# power_12V.net
KiCad netlist of a schematic drawn in Altium Designer
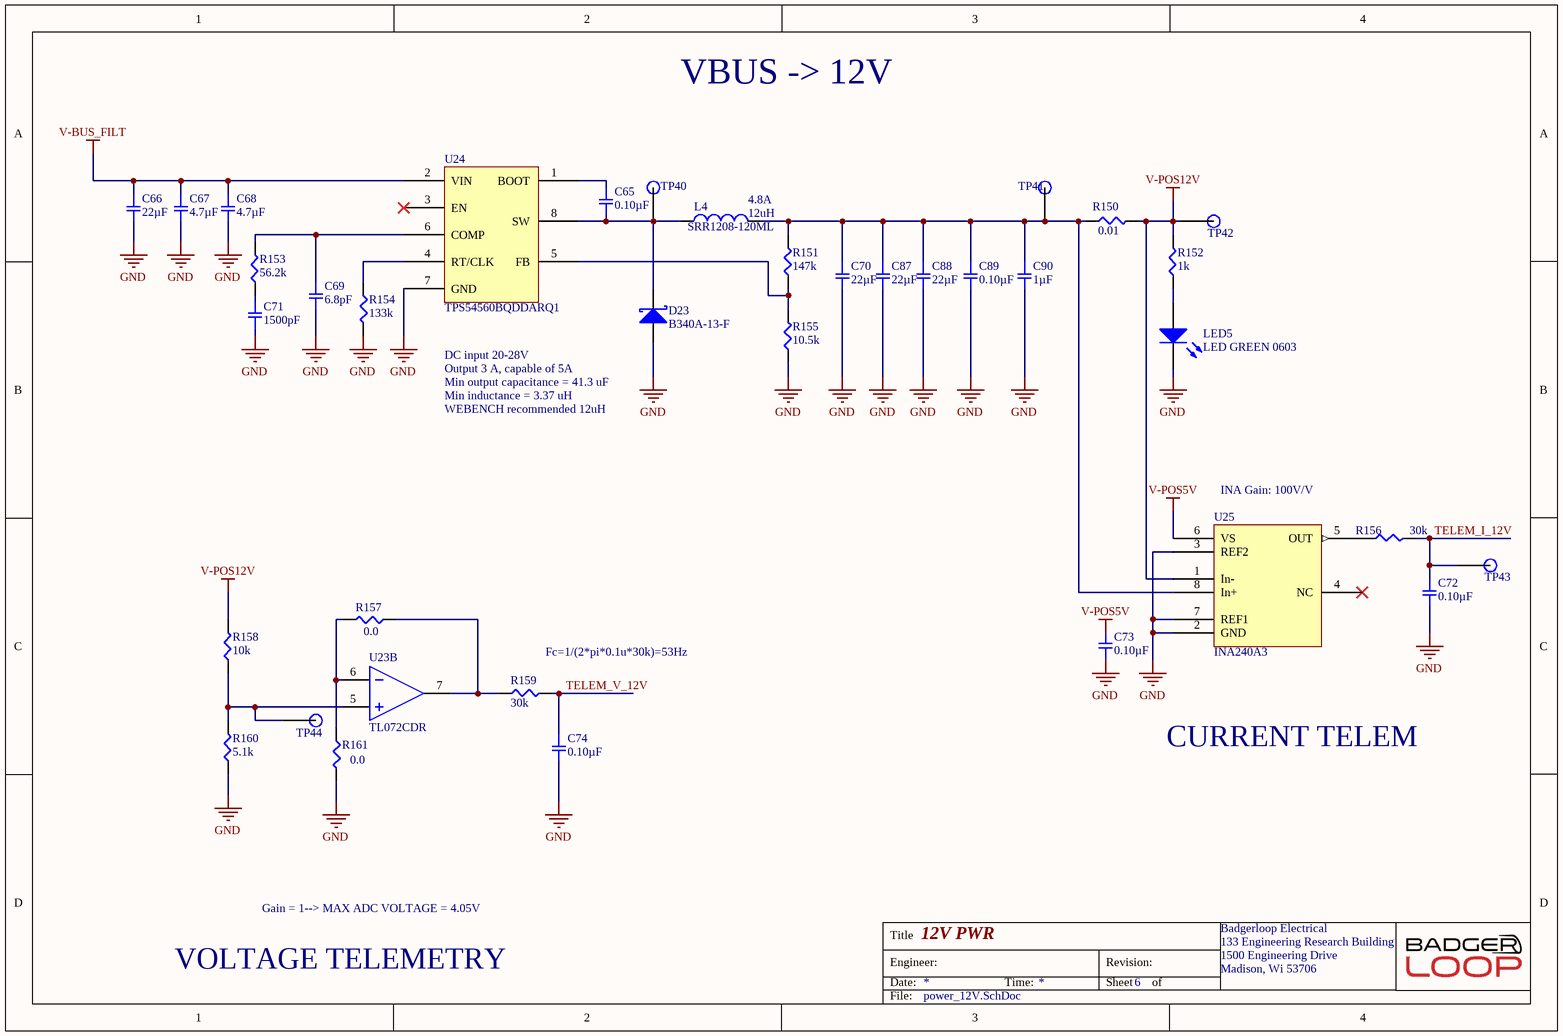
[diagram p0: power_12V.SchDoc]

(export (version "E")
  (design (tool "Eeschema 10.0.6"))
  (components
    (comp (ref "C65")
      (value "0.10µF")
      (footprint "SMD-0805C")
      (description "CAP CER 0.1UF 50V X7R 0805")
      (fields
        (field (name "DIGI-KEY PART NUMBER") "490-11955-1-ND")
        (field (name "PART NUMBER") "GCD21BR71H104KA01L")
      )
      (libsource (lib "capacitors") (part "GCD21BR71H104KA01L"))
    )
    (comp (ref "C66")
      (value "22µF")
      (footprint "SMD-1206C")
      (description "CAP CER 22UF 25V X5R 1206")
      (fields
        (field (name "DIGI-KEY PART NUMBER") "490-12451-1-ND")
        (field (name "PART NUMBER") "GRT31CR61E226ME01L")
      )
      (libsource (lib "capacitors") (part "GRT31CR61E226ME01L"))
    )
    (comp (ref "C67")
      (value "4.7µF")
      (footprint "SMD-0805C")
      (description "CAP CER 4.7UF 50V X5R 0805")
      (fields
        (field (name "DIGI-KEY PART NUMBER") "490-12395-1-ND")
        (field (name "PART NUMBER") "GRT21BR61H475ME13L")
      )
      (libsource (lib "capacitors") (part "GRT21BR61H475ME13L"))
    )
    (comp (ref "C68")
      (value "4.7µF")
      (footprint "SMD-0805C")
      (description "CAP CER 4.7UF 50V X5R 0805")
      (fields
        (field (name "DIGI-KEY PART NUMBER") "490-12395-1-ND")
        (field (name "PART NUMBER") "GRT21BR61H475ME13L")
      )
      (libsource (lib "capacitors") (part "GRT21BR61H475ME13L"))
    )
    (comp (ref "C69")
      (value "6.8pF")
      (footprint "SMD-0805C")
      (description "CAP CER 6.8PF 100V NP0 0805")
      (fields
        (field (name "DIGI-KEY PART NUMBER") "490-3596-1-ND")
        (field (name "PART NUMBER") "GQM2195C2A6R8CB01D")
      )
      (libsource (lib "capacitors") (part "GQM2195C2A6R8CB01D"))
    )
    (comp (ref "C70")
      (value "22µF")
      (footprint "SMD-1206C")
      (description "CAP CER 22UF 25V X5R 1206")
      (fields
        (field (name "DIGI-KEY PART NUMBER") "490-12451-1-ND")
        (field (name "PART NUMBER") "GRT31CR61E226ME01L")
      )
      (libsource (lib "capacitors") (part "GRT31CR61E226ME01L"))
    )
    (comp (ref "C71")
      (value "1500pF")
      (footprint "SMD-0805C")
      (description "CAP CER 1500PF 50V NP0 0805")
      (fields
        (field (name "DIGI-KEY PART NUMBER") "490-7772-1-ND")
        (field (name "PART NUMBER") "GRM2165C1H152FA01D")
      )
      (libsource (lib "capacitors") (part "GRM2165C1H152FA01D"))
    )
    (comp (ref "C72")
      (value "0.10µF")
      (footprint "SMD-0805C")
      (description "CAP CER 0.1UF 16V X7R 0805")
      (fields
        (field (name "DIGI-KEY PART NUMBER") "490-1683-1-ND")
        (field (name "PART NUMBER") "GRM219R71C104KA01D")
      )
      (libsource (lib "capacitors") (part "GRM219R71C104KA01D"))
    )
    (comp (ref "C73")
      (value "0.10µF")
      (footprint "SMD-0805C")
      (description "CAP CER 0.1UF 10V U2J 0805")
      (fields
        (field (name "DIGI-KEY PART NUMBER") "490-11592-1-ND")
        (field (name "PART NUMBER") "GRM21B7U1A104JA01L")
      )
      (libsource (lib "capacitors") (part "GRM21B7U1A104JA01L"))
    )
    (comp (ref "C74")
      (value "0.10µF")
      (footprint "SMD-0805C")
      (description "CAP CER 0.1UF 16V X7R 0805")
      (fields
        (field (name "DIGI-KEY PART NUMBER") "490-1683-1-ND")
        (field (name "PART NUMBER") "GRM219R71C104KA01D")
      )
      (libsource (lib "capacitors") (part "GRM219R71C104KA01D"))
    )
    (comp (ref "C87")
      (value "22µF")
      (footprint "SMD-1206C")
      (description "CAP CER 22UF 25V X5R 1206")
      (fields
        (field (name "DIGI-KEY PART NUMBER") "490-12451-1-ND")
        (field (name "PART NUMBER") "GRT31CR61E226ME01L")
      )
      (libsource (lib "capacitors") (part "GRT31CR61E226ME01L"))
    )
    (comp (ref "C88")
      (value "22µF")
      (footprint "SMD-1206C")
      (description "CAP CER 22UF 25V X5R 1206")
      (fields
        (field (name "DIGI-KEY PART NUMBER") "490-12451-1-ND")
        (field (name "PART NUMBER") "GRT31CR61E226ME01L")
      )
      (libsource (lib "capacitors") (part "GRT31CR61E226ME01L"))
    )
    (comp (ref "C89")
      (value "0.10µF")
      (footprint "SMD-0805C")
      (description "CAP CER 0.1UF 10V U2J 0805")
      (fields
        (field (name "DIGI-KEY PART NUMBER") "490-11592-1-ND")
        (field (name "PART NUMBER") "GRM21B7U1A104JA01L")
      )
      (libsource (lib "capacitors") (part "GRM21B7U1A104JA01L"))
    )
    (comp (ref "C90")
      (value "1µF")
      (footprint "SMD-0805C")
      (description "CAP CER 1UF 50V X7R 0805")
      (fields
        (field (name "DIGI-KEY PART NUMBER") "490-4736-1-ND")
        (field (name "PART NUMBER") "GRM21BR71H105KA12L")
      )
      (libsource (lib "capacitors") (part "GRM21BR71H105KA12L"))
    )
    (comp (ref "D23")
      (value "B340A-13-F")
      (footprint "DIOM4326X20N")
      (description "DIODE SCHOTTKY 40V 3A SMA")
      (fields (field (name "MANUFACTURER") "Diodes") (field (name "VOLTAGE") "40V"))
      (libsource (lib "misc") (part "B340A-13-F"))
    )
    (comp (ref "L4")
      (value "SRR1208-120ML")
      (footprint "INDP127127X83N")
      (description "BOURNS - SRR1208-120ML - INDUCTOR, SHIELDED, 12UH, 6.5A, 20%, SMD")
      (fields
        (field (name "MANUFACTURER") "Bourns")
        (field (name "TOLERANCE") "20%")
        (field (name "CURRENT RATING") "4.8A")
        (field (name "INDUCTANCE") "12uH")
      )
      (libsource (lib "inductor") (part "SRR1208-120ML"))
    )
    (comp (ref "LED5")
      (value "LED GREEN 0603")
      (footprint "LED 0603 GREEN")
      (fields (field (name "MANUFACTURER") "Lite-On Inc."))
      (libsource (lib "misc") (part "LED GREEN 0603"))
    )
    (comp (ref "R150")
      (value "0.01")
      (footprint "SMD-1206-RES")
      (description "RES SMD 0.01 OHM 1% 1/2W 1206")
      (fields
        (field (name "PART NUMBER") "ERJ-MP2KF10MU")
        (field (name "DIGI-KEY PART NUMBER") "P19322CT-ND")
      )
      (libsource (lib "resistors") (part "ERJ-MP2KF10MU"))
    )
    (comp (ref "R151")
      (value "147k")
      (footprint "SMD-0805-RES")
      (description "RES SMD 147K OHM 1% 1/8W 0805")
      (fields
        (field (name "PART NUMBER") "ERJ-6ENF1473V")
        (field (name "DIGI-KEY PART NUMBER") "P147KCCT-ND")
      )
      (libsource (lib "resistors") (part "ERJ-6ENF1473V"))
    )
    (comp (ref "R152")
      (value "1k")
      (footprint "SMD-0805-RES")
      (description "RES SMD 1K OHM 5% 1/2W 0805")
      (fields
        (field (name "PART NUMBER") "ERJ-P06J102V")
        (field (name "DIGI-KEY PART NUMBER") "P1.0KADCT-ND")
      )
      (libsource (lib "resistors") (part "ERJ-P06J102V"))
    )
    (comp (ref "R153")
      (value "56.2k")
      (footprint "SMD-0805-RES")
      (description "RES SMD 56.2K OHM 1% 1/8W 0805")
      (fields
        (field (name "PART NUMBER") "ERJ-6ENF5622V")
        (field (name "DIGI-KEY PART NUMBER") "P56.2KCCT-ND")
      )
      (libsource (lib "resistors") (part "ERJ-6ENF5622V"))
    )
    (comp (ref "R154")
      (value "133k")
      (footprint "SMD-0805-RES")
      (description "RES SMD 133K OHM 1% 1/8W 0805")
      (fields
        (field (name "PART NUMBER") "ERJ-6ENF1333V")
        (field (name "DIGI-KEY PART NUMBER") "P133KCCT-ND")
      )
      (libsource (lib "resistors") (part "ERJ-6ENF1333V"))
    )
    (comp (ref "R155")
      (value "10.5k")
      (footprint "SMD-0805-RES")
      (description "RES SMD 10.5K OHM 1% 1/8W 0805")
      (fields
        (field (name "PART NUMBER") "ERJ-6ENF1052V")
        (field (name "DIGI-KEY PART NUMBER") "P10.5KCCT-ND")
      )
      (libsource (lib "resistors") (part "ERJ-6ENF1052V"))
    )
    (comp (ref "R156")
      (value "30k")
      (footprint "SMD-0805-RES")
      (description "RES SMD 30K OHM 1% 1/8W 0805")
      (fields
        (field (name "PART NUMBER") "ERJ-6ENF3002V")
        (field (name "DIGI-KEY PART NUMBER") "P30.0KCCT-ND")
      )
      (libsource (lib "resistors") (part "ERJ-6ENF3002V"))
    )
    (comp (ref "R157")
      (value "0.0")
      (footprint "SMD-0805-RES")
      (description "RES SMD 0.0 OHM JUMPER 1/8W 0805")
      (fields (field (name "PART NUMBER") "ERJ-6GEY0R00V") (field (name "DIGI-KEY PART NUMBER") "P0.0ACT-ND"))
      (libsource (lib "resistors") (part "ERJ-6GEY0R00V"))
    )
    (comp (ref "R158")
      (value "10k")
      (footprint "SMD-0805-RES")
      (description "RES SMD 10K OHM 5% 1/2W 0805")
      (fields (field (name "PART NUMBER") "ERJ-P06J103V") (field (name "DIGI-KEY PART NUMBER") "P10KADCT-ND"))
      (libsource (lib "resistors") (part "ERJ-P06J103V"))
    )
    (comp (ref "R159")
      (value "30k")
      (footprint "SMD-0805-RES")
      (description "RES SMD 30K OHM 5% 1/2W 0805")
      (fields (field (name "PART NUMBER") "ERJ-P06J303V") (field (name "DIGI-KEY PART NUMBER") "P30KADCT-ND"))
      (libsource (lib "resistors") (part "ERJ-P06J303V"))
    )
    (comp (ref "R160")
      (value "5.1k")
      (footprint "SMD-0805-RES")
      (description "RES SMD 5.1K OHM 1% 1/8W 0805")
      (fields
        (field (name "PART NUMBER") "ERJ-6ENF5101V")
        (field (name "DIGI-KEY PART NUMBER") "P5.10KCCT-ND")
      )
      (libsource (lib "resistors") (part "ERJ-6ENF5101V"))
    )
    (comp (ref "R161")
      (value "0.0")
      (footprint "SMD-0805-RES")
      (description "RES SMD 0.0 OHM JUMPER 1/8W 0805")
      (fields (field (name "PART NUMBER") "ERJ-6GEY0R00V") (field (name "DIGI-KEY PART NUMBER") "P0.0ACT-ND"))
      (libsource (lib "resistors") (part "ERJ-6GEY0R00V"))
    )
    (comp (ref "TP40")
      (value "TP")
      (footprint "Test Point")
      (description "SMD TEST POINT")
      (libsource (lib "misc") (part "TP"))
    )
    (comp (ref "TP41")
      (value "TP")
      (footprint "Test Point")
      (description "SMD TEST POINT")
      (libsource (lib "misc") (part "TP"))
    )
    (comp (ref "TP42")
      (value "TP")
      (footprint "Test Point")
      (description "SMD TEST POINT")
      (libsource (lib "misc") (part "TP"))
    )
    (comp (ref "TP43")
      (value "TP")
      (footprint "Test Point")
      (description "SMD TEST POINT")
      (libsource (lib "misc") (part "TP"))
    )
    (comp (ref "TP44")
      (value "TP")
      (footprint "Test Point")
      (description "SMD TEST POINT")
      (libsource (lib "misc") (part "TP"))
    )
    (comp (ref "U23")
      (value "TL072CDR")
      (footprint "SOP127P600X175-8N")
      (description "IC OPAMP JFET 3MHZ 8SOIC")
      (fields (field (name "MANUFACTURER") "Texas Instruments"))
      (libsource (lib "ic") (part "TL072CDR"))
    )
    (comp (ref "U24")
      (value "TPS54560BQDDARQ1")
      (footprint "SOP127P600X175-8N - Thermal Pad")
      (description "IC REG BUCK SPLT ADJ 5A 8PWRSOIC")
      (fields (field (name "MANUFACTURER") "Texas Instruments"))
      (libsource (lib "ic") (part "TPS54560BQDDARQ1"))
    )
    (comp (ref "U25")
      (value "INA240A3")
      (footprint "SOIC127P600X175-8N")
      (description "IC AMP CURRENT SENSE 8-TSSOP 100V/V")
      (fields (field (name "MANUFACTURER") "Texas Instruments"))
      (libsource (lib "ic") (part "INA240A3"))
    )
  )
  (nets
    (net (code "1") (name "/TELEM_I_12V") (class "Default")
      (node (ref "C72") (pin "1") (pinfunction "1_1") (pintype "passive"))
      (node (ref "R156") (pin "2") (pinfunction "2_2") (pintype "passive"))
      (node (ref "TP43") (pin "1") (pinfunction "1_1") (pintype "passive"))
    )
    (net (code "2") (name "/TELEM_V_12V") (class "Default")
      (node (ref "C74") (pin "1") (pinfunction "1_1") (pintype "passive"))
      (node (ref "R159") (pin "2") (pinfunction "2_2") (pintype "passive"))
    )
    (net (code "3") (name "GND") (class "Default")
      (node (ref "C66") (pin "2") (pinfunction "2_2") (pintype "passive"))
      (node (ref "C67") (pin "2") (pinfunction "2_2") (pintype "passive"))
      (node (ref "C68") (pin "2") (pinfunction "2_2") (pintype "passive"))
      (node (ref "C69") (pin "2") (pinfunction "2_2") (pintype "passive"))
      (node (ref "C70") (pin "2") (pinfunction "2_2") (pintype "passive"))
      (node (ref "C71") (pin "1") (pinfunction "1_1") (pintype "passive"))
      (node (ref "C72") (pin "2") (pinfunction "2_2") (pintype "passive"))
      (node (ref "C73") (pin "1") (pinfunction "1_1") (pintype "passive"))
      (node (ref "C74") (pin "2") (pinfunction "2_2") (pintype "passive"))
      (node (ref "C87") (pin "2") (pinfunction "2_2") (pintype "passive"))
      (node (ref "C88") (pin "2") (pinfunction "2_2") (pintype "passive"))
      (node (ref "C89") (pin "2") (pinfunction "2_2") (pintype "passive"))
      (node (ref "C90") (pin "2") (pinfunction "2_2") (pintype "passive"))
      (node (ref "D23") (pin "2") (pinfunction "A_2") (pintype "passive"))
      (node (ref "LED5") (pin "2") (pinfunction "K_2") (pintype "passive"))
      (node (ref "R154") (pin "2") (pinfunction "2_2") (pintype "passive"))
      (node (ref "R155") (pin "1") (pinfunction "1_1") (pintype "passive"))
      (node (ref "R160") (pin "1") (pinfunction "1_1") (pintype "passive"))
      (node (ref "R161") (pin "2") (pinfunction "2_2") (pintype "passive"))
      (node (ref "U24") (pin "7") (pinfunction "GND_7") (pintype "passive"))
      (node (ref "U25") (pin "2") (pinfunction "GND_2") (pintype "power_in"))
      (node (ref "U25") (pin "3") (pinfunction "REF2_3") (pintype "passive"))
      (node (ref "U25") (pin "7") (pinfunction "REF1_7") (pintype "passive"))
    )
    (net (code "4") (name "Net-(C71-Pad2)") (class "Default")
      (node (ref "C71") (pin "2") (pinfunction "2_2") (pintype "passive"))
      (node (ref "R153") (pin "1") (pinfunction "1_1") (pintype "passive"))
    )
    (net (code "5") (name "Net-(D23-K)") (class "Default")
      (node (ref "C65") (pin "2") (pinfunction "2_2") (pintype "passive"))
      (node (ref "D23") (pin "1") (pinfunction "K_1") (pintype "passive"))
      (node (ref "L4") (pin "1") (pinfunction "1_1") (pintype "passive"))
      (node (ref "TP40") (pin "1") (pinfunction "1_1") (pintype "passive"))
      (node (ref "U24") (pin "8") (pinfunction "SW_8") (pintype "passive"))
    )
    (net (code "6") (name "Net-(LED5-A)") (class "Default")
      (node (ref "LED5") (pin "1") (pinfunction "A_1") (pintype "passive"))
      (node (ref "R152") (pin "1") (pinfunction "1_1") (pintype "passive"))
    )
    (net (code "7") (name "Net-(U23B-IN+)") (class "Default")
      (node (ref "R158") (pin "1") (pinfunction "1_1") (pintype "passive"))
      (node (ref "R160") (pin "2") (pinfunction "2_2") (pintype "passive"))
      (node (ref "TP44") (pin "1") (pinfunction "1_1") (pintype "passive"))
      (node (ref "U23") (pin "5") (pinfunction "IN+_5") (pintype "passive"))
    )
    (net (code "8") (name "Net-(U23B-IN-)") (class "Default")
      (node (ref "R157") (pin "2") (pinfunction "2_2") (pintype "passive"))
      (node (ref "R161") (pin "1") (pinfunction "1_1") (pintype "passive"))
      (node (ref "U23") (pin "6") (pinfunction "IN-_6") (pintype "passive"))
    )
    (net (code "9") (name "Net-(U23B-OUT)") (class "Default")
      (node (ref "R157") (pin "1") (pinfunction "1_1") (pintype "passive"))
      (node (ref "R159") (pin "1") (pinfunction "1_1") (pintype "passive"))
      (node (ref "U23") (pin "7") (pinfunction "OUT_7") (pintype "passive"))
    )
    (net (code "10") (name "Net-(U24-BOOT)") (class "Default")
      (node (ref "C65") (pin "1") (pinfunction "1_1") (pintype "passive"))
      (node (ref "U24") (pin "1") (pinfunction "BOOT_1") (pintype "passive"))
    )
    (net (code "11") (name "Net-(U24-COMP)") (class "Default")
      (node (ref "C69") (pin "1") (pinfunction "1_1") (pintype "passive"))
      (node (ref "R153") (pin "2") (pinfunction "2_2") (pintype "passive"))
      (node (ref "U24") (pin "6") (pinfunction "COMP_6") (pintype "passive"))
    )
    (net (code "12") (name "Net-(U24-FB)") (class "Default")
      (node (ref "R151") (pin "1") (pinfunction "1_1") (pintype "passive"))
      (node (ref "R155") (pin "2") (pinfunction "2_2") (pintype "passive"))
      (node (ref "U24") (pin "5") (pinfunction "FB_5") (pintype "passive"))
    )
    (net (code "13") (name "Net-(U24-RT{slash}CLK)") (class "Default")
      (node (ref "R154") (pin "1") (pinfunction "1_1") (pintype "passive"))
      (node (ref "U24") (pin "4") (pinfunction "RT/CLK_4") (pintype "passive"))
    )
    (net (code "14") (name "Net-(U25-In+)") (class "Default")
      (node (ref "C70") (pin "1") (pinfunction "1_1") (pintype "passive"))
      (node (ref "C87") (pin "1") (pinfunction "1_1") (pintype "passive"))
      (node (ref "C88") (pin "1") (pinfunction "1_1") (pintype "passive"))
      (node (ref "C89") (pin "1") (pinfunction "1_1") (pintype "passive"))
      (node (ref "C90") (pin "1") (pinfunction "1_1") (pintype "passive"))
      (node (ref "L4") (pin "2") (pinfunction "2_2") (pintype "passive"))
      (node (ref "R150") (pin "1") (pinfunction "1_1") (pintype "passive"))
      (node (ref "R151") (pin "2") (pinfunction "2_2") (pintype "passive"))
      (node (ref "TP41") (pin "1") (pinfunction "1_1") (pintype "passive"))
      (node (ref "U25") (pin "8") (pinfunction "In+_8") (pintype "passive"))
    )
    (net (code "15") (name "Net-(U25-OUT)") (class "Default")
      (node (ref "R156") (pin "1") (pinfunction "1_1") (pintype "passive"))
      (node (ref "U25") (pin "5") (pinfunction "OUT_5") (pintype "output"))
    )
    (net (code "16") (name "V-BUS_FILT") (class "Default")
      (node (ref "C66") (pin "1") (pinfunction "1_1") (pintype "passive"))
      (node (ref "C67") (pin "1") (pinfunction "1_1") (pintype "passive"))
      (node (ref "C68") (pin "1") (pinfunction "1_1") (pintype "passive"))
      (node (ref "U24") (pin "2") (pinfunction "VIN_2") (pintype "passive"))
    )
    (net (code "17") (name "V-POS5V") (class "Default")
      (node (ref "C73") (pin "2") (pinfunction "2_2") (pintype "passive"))
      (node (ref "U25") (pin "6") (pinfunction "VS_6") (pintype "power_in"))
    )
    (net (code "18") (name "V-POS12V") (class "Default")
      (node (ref "R150") (pin "2") (pinfunction "2_2") (pintype "passive"))
      (node (ref "R152") (pin "2") (pinfunction "2_2") (pintype "passive"))
      (node (ref "R158") (pin "2") (pinfunction "2_2") (pintype "passive"))
      (node (ref "TP42") (pin "1") (pinfunction "1_1") (pintype "passive"))
      (node (ref "U25") (pin "1") (pinfunction "In-_1") (pintype "passive"))
    )
    (net (code "19") (name "unconnected-(U24-EN-Pad3)") (class "Default")
      (node (ref "U24") (pin "3") (pinfunction "EN_3") (pintype "passive+no_connect"))
    )
    (net (code "20") (name "unconnected-(U25-NC-Pad4)") (class "Default")
      (node (ref "U25") (pin "4") (pinfunction "NC_4") (pintype "passive+no_connect"))
    )
  )
)
